# calchack.net
KiCad netlist of a schematic drawn in EAGLE
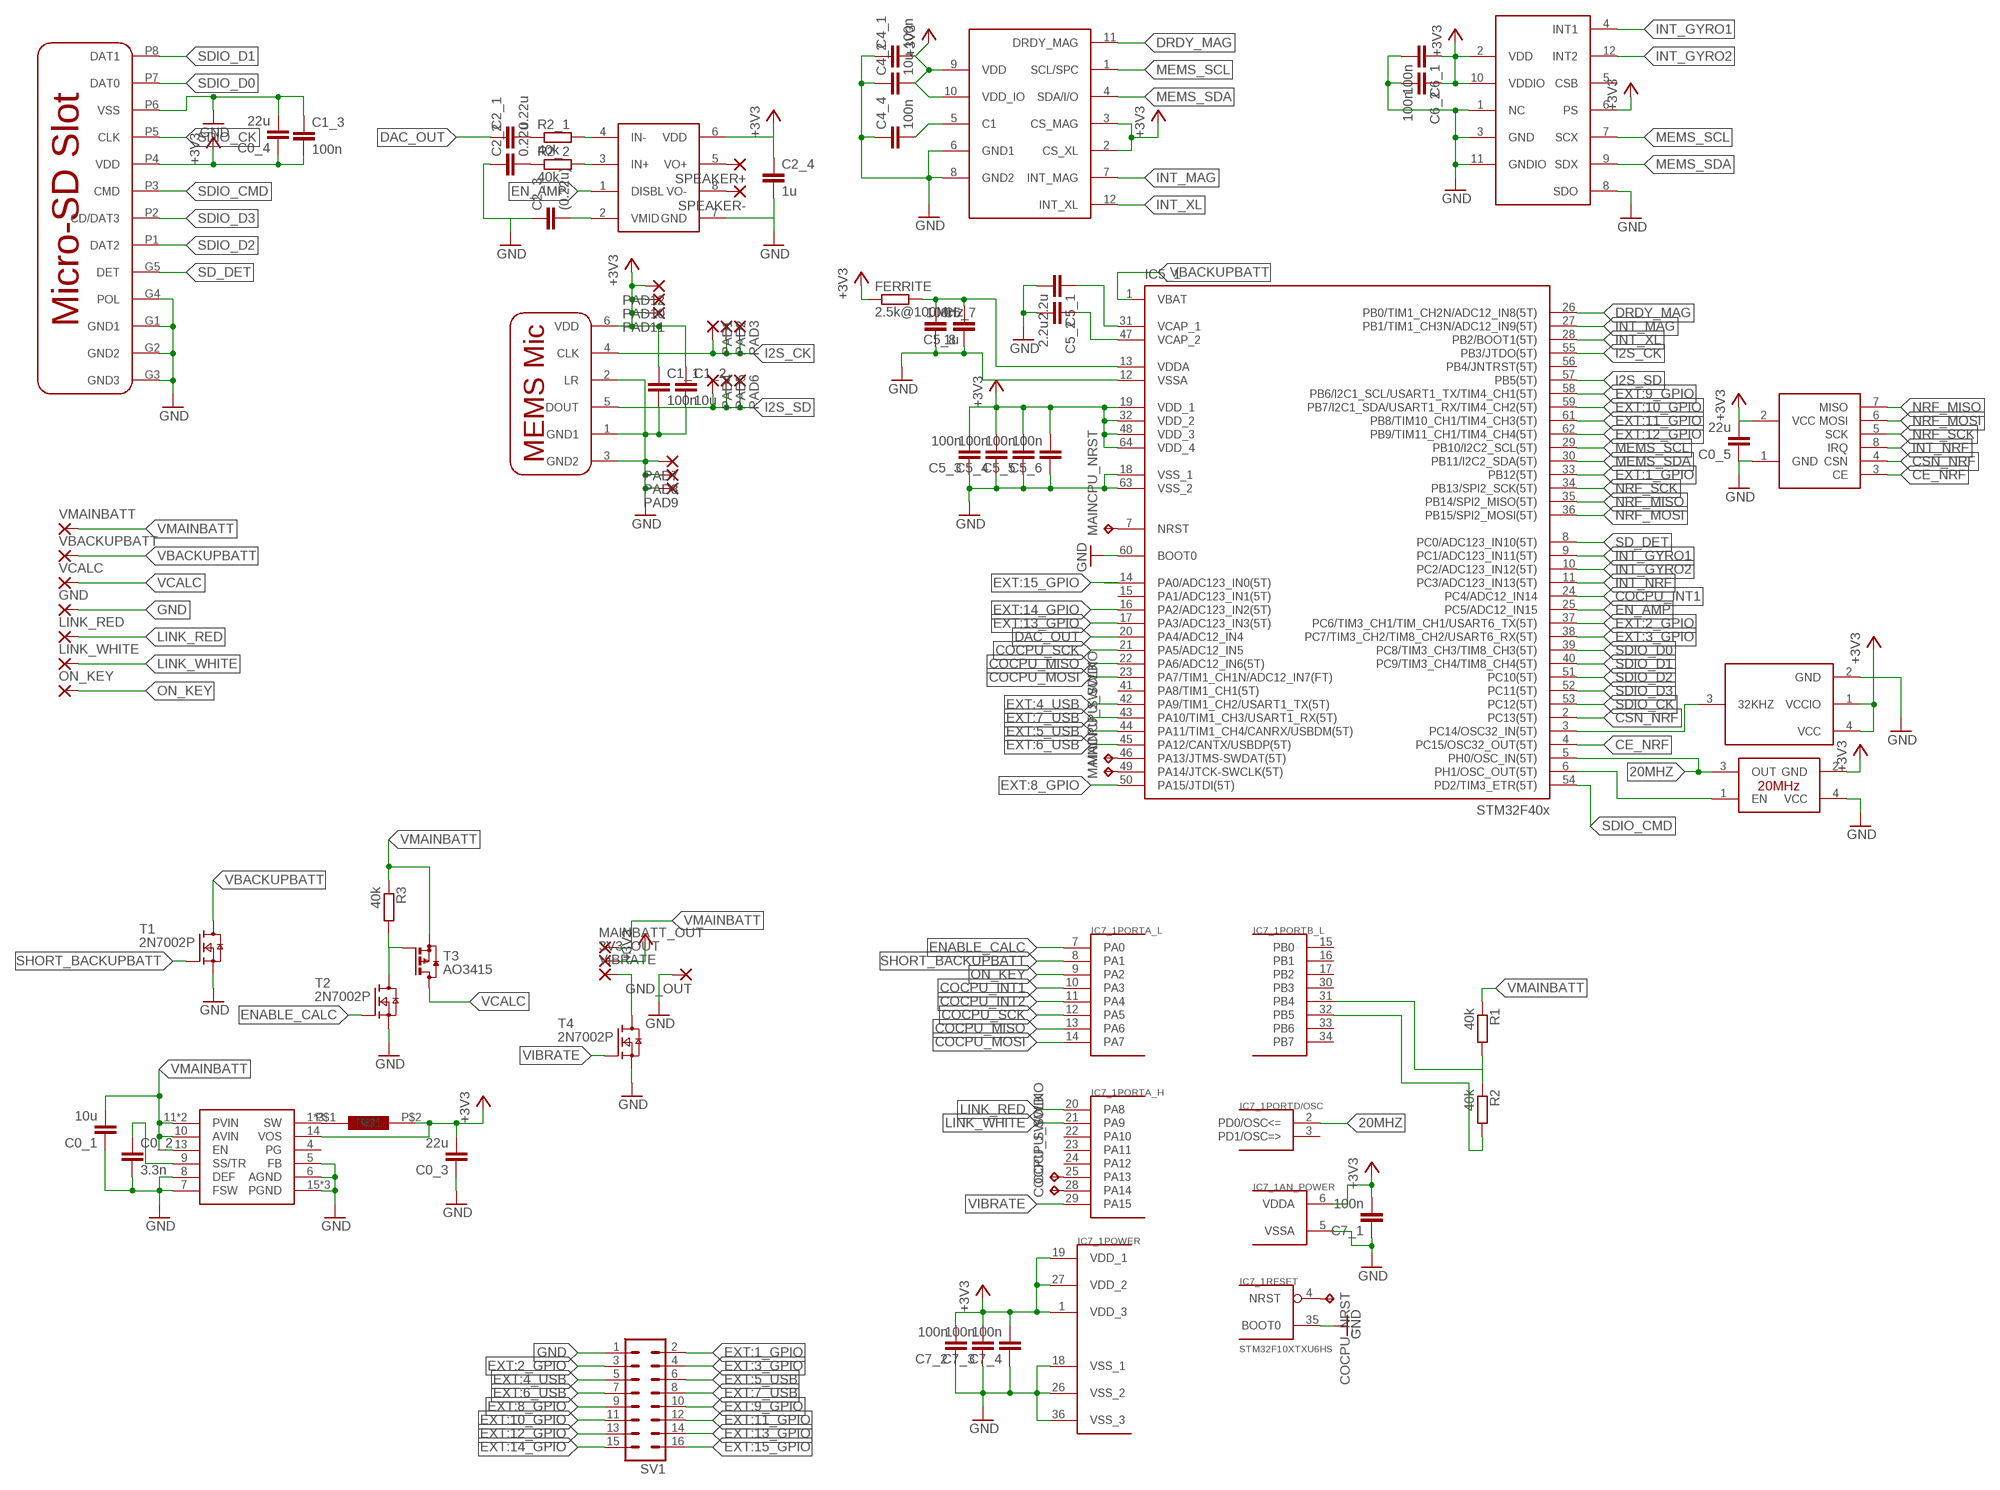
[diagram p0: schematic, sheet 1]

(export (version "E")
  (design (tool "Eeschema 10.0.6"))
  (components
    (comp (ref "3V3_OUT")
      (value "1,6/0,8")
      (footprint "eagle-import:1,6_0,8")
      (libsource (lib "eagle-import") (part "1,6/0,8"))
    )
    (comp (ref "C0_1")
      (value "10u")
      (footprint "eagle-import:C0805")
      (libsource (lib "eagle-import") (part "C-EUC0805"))
    )
    (comp (ref "C0_2")
      (value "3.3n")
      (footprint "eagle-import:C0603")
      (libsource (lib "eagle-import") (part "C-EUC0603"))
    )
    (comp (ref "C0_3")
      (value "22u")
      (footprint "eagle-import:C0805")
      (libsource (lib "eagle-import") (part "C-EUC0805"))
    )
    (comp (ref "C0_4")
      (value "22u")
      (footprint "eagle-import:C0805")
      (libsource (lib "eagle-import") (part "C-EUC0805"))
    )
    (comp (ref "C0_5")
      (value "22u")
      (footprint "eagle-import:C0805")
      (libsource (lib "eagle-import") (part "C-EUC0805"))
    )
    (comp (ref "C1_1")
      (value "100n")
      (footprint "eagle-import:C0603")
      (libsource (lib "eagle-import") (part "C-EUC0603"))
    )
    (comp (ref "C1_2")
      (value "10u")
      (footprint "eagle-import:C0603")
      (libsource (lib "eagle-import") (part "C-EUC0603"))
    )
    (comp (ref "C1_3")
      (value "100n")
      (footprint "eagle-import:C0603")
      (libsource (lib "eagle-import") (part "C-EUC0603"))
    )
    (comp (ref "C2_1")
      (value "0.22u")
      (footprint "eagle-import:C0603")
      (libsource (lib "eagle-import") (part "C-EUC0603"))
    )
    (comp (ref "C2_2")
      (value "0.22u")
      (footprint "eagle-import:C0603")
      (libsource (lib "eagle-import") (part "C-EUC0603"))
    )
    (comp (ref "C2_3")
      (value "(0.22u)")
      (footprint "eagle-import:C0603")
      (libsource (lib "eagle-import") (part "C-EUC0603"))
    )
    (comp (ref "C2_4")
      (value "1u")
      (footprint "eagle-import:C0603")
      (libsource (lib "eagle-import") (part "C-EUC0603"))
    )
    (comp (ref "C4_1")
      (value "100n")
      (footprint "eagle-import:C0603")
      (libsource (lib "eagle-import") (part "C-EUC0603"))
    )
    (comp (ref "C4_2")
      (value "10u")
      (footprint "eagle-import:C0603")
      (libsource (lib "eagle-import") (part "C-EUC0603"))
    )
    (comp (ref "C4_4")
      (value "100n")
      (footprint "eagle-import:C0603")
      (libsource (lib "eagle-import") (part "C-EUC0603"))
    )
    (comp (ref "C5_1")
      (value "2.2u")
      (footprint "eagle-import:C0603")
      (libsource (lib "eagle-import") (part "C-EUC0603"))
    )
    (comp (ref "C5_2")
      (value "2.2u")
      (footprint "eagle-import:C0603")
      (libsource (lib "eagle-import") (part "C-EUC0603"))
    )
    (comp (ref "C5_3")
      (value "100n")
      (footprint "eagle-import:C0603")
      (libsource (lib "eagle-import") (part "C-EUC0603"))
    )
    (comp (ref "C5_4")
      (value "100n")
      (footprint "eagle-import:C0603")
      (libsource (lib "eagle-import") (part "C-EUC0603"))
    )
    (comp (ref "C5_5")
      (value "100n")
      (footprint "eagle-import:C0603")
      (libsource (lib "eagle-import") (part "C-EUC0603"))
    )
    (comp (ref "C5_6")
      (value "100n")
      (footprint "eagle-import:C0603")
      (libsource (lib "eagle-import") (part "C-EUC0603"))
    )
    (comp (ref "C5_7")
      (value "1u")
      (footprint "eagle-import:C0603")
      (libsource (lib "eagle-import") (part "C-EUC0603"))
    )
    (comp (ref "C5_8")
      (value "100n")
      (footprint "eagle-import:C0603")
      (libsource (lib "eagle-import") (part "C-EUC0603"))
    )
    (comp (ref "C6_1")
      (value "100n")
      (footprint "eagle-import:C0603")
      (libsource (lib "eagle-import") (part "C-EUC0603"))
    )
    (comp (ref "C6_2")
      (value "100n")
      (footprint "eagle-import:C0603")
      (libsource (lib "eagle-import") (part "C-EUC0603"))
    )
    (comp (ref "C7_1")
      (value "100n")
      (footprint "eagle-import:C0603")
      (libsource (lib "eagle-import") (part "C-EUC0603"))
    )
    (comp (ref "C7_2")
      (value "100n")
      (footprint "eagle-import:C0603")
      (libsource (lib "eagle-import") (part "C-EUC0603"))
    )
    (comp (ref "C7_3")
      (value "100n")
      (footprint "eagle-import:C0603")
      (libsource (lib "eagle-import") (part "C-EUC0603"))
    )
    (comp (ref "C7_4")
      (value "100n")
      (footprint "eagle-import:C0603")
      (libsource (lib "eagle-import") (part "C-EUC0603"))
    )
    (comp (ref "COCPU_NRST")
      (value "TPTP10SQ")
      (footprint "eagle-import:TP10SQ")
      (libsource (lib "eagle-import") (part "TPTP10SQ"))
    )
    (comp (ref "COCPU_SWCLK")
      (value "TPTP10SQ")
      (footprint "eagle-import:TP10SQ")
      (libsource (lib "eagle-import") (part "TPTP10SQ"))
    )
    (comp (ref "COCPU_SWDIO")
      (value "TPTP10SQ")
      (footprint "eagle-import:TP10SQ")
      (libsource (lib "eagle-import") (part "TPTP10SQ"))
    )
    (comp (ref "FERRITE")
      (value "2.5k@100MHz")
      (footprint "eagle-import:R0603")
      (libsource (lib "eagle-import") (part "R-EU_R0603"))
    )
    (comp (ref "GND")
      (value "1,6/0,8")
      (footprint "eagle-import:1,6_0,8")
      (libsource (lib "eagle-import") (part "1,6/0,8"))
    )
    (comp (ref "GND_OUT")
      (value "1,6/0,8")
      (footprint "eagle-import:1,6_0,8")
      (libsource (lib "eagle-import") (part "1,6/0,8"))
    )
    (comp (ref "IC0_1")
      (value "TPS62142")
      (footprint "eagle-import:TPS62142")
      (libsource (lib "eagle-import") (part "TPS62142"))
    )
    (comp (ref "IC1_1")
      (value "MP45DT02")
      (footprint "eagle-import:MP45DT02")
      (libsource (lib "eagle-import") (part "MP45DT02"))
    )
    (comp (ref "IC2_1")
      (value "TPA6211A1")
      (footprint "eagle-import:TPA6211A1")
      (libsource (lib "eagle-import") (part "TPA6211A1"))
    )
    (comp (ref "IC3_1")
      (value "475710001")
      (footprint "eagle-import:475710001")
      (libsource (lib "eagle-import") (part "475710001"))
    )
    (comp (ref "IC4_1")
      (value "LSM303C")
      (footprint "eagle-import:LSM303C")
      (libsource (lib "eagle-import") (part "LSM303C"))
    )
    (comp (ref "IC5_1")
      (value "STM32F405R")
      (footprint "eagle-import:TQFP64")
      (libsource (lib "eagle-import") (part "STM32F405R"))
    )
    (comp (ref "IC6_1")
      (value "BMG160")
      (footprint "eagle-import:BMG160")
      (libsource (lib "eagle-import") (part "BMG160"))
    )
    (comp (ref "IC7_1")
      (value "STM32F10XTXU6HS")
      (footprint "eagle-import:VFQFPN36-HS")
      (libsource (lib "eagle-import") (part "STM32F10XTXU6HS"))
    )
    (comp (ref "L0_1")
      (value "IHLP1212BZER2R2M11")
      (footprint "eagle-import:IHLP1212BZER2R2M11")
      (libsource (lib "eagle-import") (part "IHLP1212BZER2R2M11"))
    )
    (comp (ref "LINK_RED")
      (value "1,6/0,8")
      (footprint "eagle-import:1,6_0,8")
      (libsource (lib "eagle-import") (part "1,6/0,8"))
    )
    (comp (ref "LINK_WHITE")
      (value "1,6/0,8")
      (footprint "eagle-import:1,6_0,8")
      (libsource (lib "eagle-import") (part "1,6/0,8"))
    )
    (comp (ref "MAINBATT_OUT")
      (value "1,6/0,8")
      (footprint "eagle-import:1,6_0,8")
      (libsource (lib "eagle-import") (part "1,6/0,8"))
    )
    (comp (ref "MAINCPU_NRST")
      (value "TPTP10SQ")
      (footprint "eagle-import:TP10SQ")
      (libsource (lib "eagle-import") (part "TPTP10SQ"))
    )
    (comp (ref "MAINCPU_SWCLK")
      (value "TPTP10SQ")
      (footprint "eagle-import:TP10SQ")
      (libsource (lib "eagle-import") (part "TPTP10SQ"))
    )
    (comp (ref "MAINCPU_SWDIO")
      (value "TPTP10SQ")
      (footprint "eagle-import:TP10SQ")
      (libsource (lib "eagle-import") (part "TPTP10SQ"))
    )
    (comp (ref "NRF24L01")
      (value "NRF24L01")
      (footprint "eagle-import:NRF24L01")
      (libsource (lib "eagle-import") (part "NRF24L01"))
    )
    (comp (ref "ON_KEY")
      (value "1,6/0,8")
      (footprint "eagle-import:1,6_0,8")
      (libsource (lib "eagle-import") (part "1,6/0,8"))
    )
    (comp (ref "OSC5_1")
      (value "SG-3030JC")
      (footprint "eagle-import:SG-3030JC")
      (libsource (lib "eagle-import") (part "SG-3030JC"))
    )
    (comp (ref "PAD1")
      (value "1,6/0,8")
      (footprint "eagle-import:1,6_0,8")
      (libsource (lib "eagle-import") (part "1,6/0,8"))
    )
    (comp (ref "PAD2")
      (value "1,6/0,8")
      (footprint "eagle-import:1,6_0,8")
      (libsource (lib "eagle-import") (part "1,6/0,8"))
    )
    (comp (ref "PAD3")
      (value "1,6/0,8")
      (footprint "eagle-import:1,6_0,8")
      (libsource (lib "eagle-import") (part "1,6/0,8"))
    )
    (comp (ref "PAD4")
      (value "1,6/0,8")
      (footprint "eagle-import:1,6_0,8")
      (libsource (lib "eagle-import") (part "1,6/0,8"))
    )
    (comp (ref "PAD5")
      (value "1,6/0,8")
      (footprint "eagle-import:1,6_0,8")
      (libsource (lib "eagle-import") (part "1,6/0,8"))
    )
    (comp (ref "PAD6")
      (value "1,6/0,8")
      (footprint "eagle-import:1,6_0,8")
      (libsource (lib "eagle-import") (part "1,6/0,8"))
    )
    (comp (ref "PAD7")
      (value "1,6/0,8")
      (footprint "eagle-import:1,6_0,8")
      (libsource (lib "eagle-import") (part "1,6/0,8"))
    )
    (comp (ref "PAD8")
      (value "1,6/0,8")
      (footprint "eagle-import:1,6_0,8")
      (libsource (lib "eagle-import") (part "1,6/0,8"))
    )
    (comp (ref "PAD9")
      (value "1,6/0,8")
      (footprint "eagle-import:1,6_0,8")
      (libsource (lib "eagle-import") (part "1,6/0,8"))
    )
    (comp (ref "PAD10")
      (value "1,6/0,8")
      (footprint "eagle-import:1,6_0,8")
      (libsource (lib "eagle-import") (part "1,6/0,8"))
    )
    (comp (ref "PAD11")
      (value "1,6/0,8")
      (footprint "eagle-import:1,6_0,8")
      (libsource (lib "eagle-import") (part "1,6/0,8"))
    )
    (comp (ref "PAD12")
      (value "1,6/0,8")
      (footprint "eagle-import:1,6_0,8")
      (libsource (lib "eagle-import") (part "1,6/0,8"))
    )
    (comp (ref "R1")
      (value "40k")
      (footprint "eagle-import:R0603")
      (libsource (lib "eagle-import") (part "R-EU_R0603"))
    )
    (comp (ref "R2")
      (value "40k")
      (footprint "eagle-import:R0603")
      (libsource (lib "eagle-import") (part "R-EU_R0603"))
    )
    (comp (ref "R2_1")
      (value "40k")
      (footprint "eagle-import:R0603")
      (libsource (lib "eagle-import") (part "R-EU_R0603"))
    )
    (comp (ref "R2_2")
      (value "40k")
      (footprint "eagle-import:R0603")
      (libsource (lib "eagle-import") (part "R-EU_R0603"))
    )
    (comp (ref "R3")
      (value "40k")
      (footprint "eagle-import:R0603")
      (libsource (lib "eagle-import") (part "R-EU_R0603"))
    )
    (comp (ref "SPEAKER+")
      (value "1,6/0,8")
      (footprint "eagle-import:1,6_0,8")
      (libsource (lib "eagle-import") (part "1,6/0,8"))
    )
    (comp (ref "SPEAKER-")
      (value "1,6/0,8")
      (footprint "eagle-import:1,6_0,8")
      (libsource (lib "eagle-import") (part "1,6/0,8"))
    )
    (comp (ref "SV1")
      (value "MA08-2")
      (footprint "eagle-import:MA08-2")
      (libsource (lib "eagle-import") (part "MA08-2"))
    )
    (comp (ref "T1")
      (value "2N7002P")
      (footprint "eagle-import:SOT23")
      (libsource (lib "eagle-import") (part "2N7002P"))
    )
    (comp (ref "T2")
      (value "2N7002P")
      (footprint "eagle-import:SOT23")
      (libsource (lib "eagle-import") (part "2N7002P"))
    )
    (comp (ref "T3")
      (value "AO3415")
      (footprint "eagle-import:AO3415")
      (libsource (lib "eagle-import") (part "AO3415"))
    )
    (comp (ref "T4")
      (value "2N7002P")
      (footprint "eagle-import:SOT23")
      (libsource (lib "eagle-import") (part "2N7002P"))
    )
    (comp (ref "U$1")
      (value "ASDMB-20.000MHZ-LC-T")
      (footprint "eagle-import:ASDMB-20.000MHZ-LC-T")
      (libsource (lib "eagle-import") (part "ASDMB-20.000MHZ-LC-T"))
    )
    (comp (ref "VBACKUPBATT")
      (value "1,6/0,8")
      (footprint "eagle-import:1,6_0,8")
      (libsource (lib "eagle-import") (part "1,6/0,8"))
    )
    (comp (ref "VCALC")
      (value "1,6/0,8")
      (footprint "eagle-import:1,6_0,8")
      (libsource (lib "eagle-import") (part "1,6/0,8"))
    )
    (comp (ref "VIBRATE")
      (value "1,6/0,8")
      (footprint "eagle-import:1,6_0,8")
      (libsource (lib "eagle-import") (part "1,6/0,8"))
    )
    (comp (ref "VMAINBATT")
      (value "1,6/0,8")
      (footprint "eagle-import:1,6_0,8")
      (libsource (lib "eagle-import") (part "1,6/0,8"))
    )
  )
  (nets
    (net (code "1") (name "+3V3") (class "Default")
      (node (ref "3V3_OUT") (pin "1") (pinfunction "P_1") (pintype "passive"))
      (node (ref "C0_3") (pin "2") (pinfunction "2_2") (pintype "passive"))
      (node (ref "C0_4") (pin "1") (pinfunction "1_1") (pintype "passive"))
      (node (ref "C0_5") (pin "2") (pinfunction "2_2") (pintype "passive"))
      (node (ref "C1_1") (pin "1") (pinfunction "1_1") (pintype "passive"))
      (node (ref "C1_2") (pin "1") (pinfunction "1_1") (pintype "passive"))
      (node (ref "C1_3") (pin "2") (pinfunction "2_2") (pintype "passive"))
      (node (ref "C2_4") (pin "1") (pinfunction "1_1") (pintype "passive"))
      (node (ref "C4_1") (pin "2") (pinfunction "2_2") (pintype "passive"))
      (node (ref "C4_2") (pin "2") (pinfunction "2_2") (pintype "passive"))
      (node (ref "C5_3") (pin "2") (pinfunction "2_2") (pintype "passive"))
      (node (ref "C5_4") (pin "2") (pinfunction "2_2") (pintype "passive"))
      (node (ref "C5_5") (pin "2") (pinfunction "2_2") (pintype "passive"))
      (node (ref "C5_6") (pin "2") (pinfunction "2_2") (pintype "passive"))
      (node (ref "C6_1") (pin "1") (pinfunction "1_1") (pintype "passive"))
      (node (ref "C6_2") (pin "1") (pinfunction "1_1") (pintype "passive"))
      (node (ref "C7_1") (pin "2") (pinfunction "2_2") (pintype "passive"))
      (node (ref "C7_2") (pin "2") (pinfunction "2_2") (pintype "passive"))
      (node (ref "C7_3") (pin "2") (pinfunction "2_2") (pintype "passive"))
      (node (ref "C7_4") (pin "2") (pinfunction "2_2") (pintype "passive"))
      (node (ref "FERRITE") (pin "1") (pinfunction "1_1") (pintype "passive"))
      (node (ref "IC0_1") (pin "14") (pinfunction "VOS_14") (pintype "bidirectional"))
      (node (ref "IC1_1") (pin "6") (pinfunction "VDD_6") (pintype "bidirectional"))
      (node (ref "IC2_1") (pin "6") (pinfunction "VDD_6") (pintype "bidirectional"))
      (node (ref "IC3_1") (pin "P4") (pinfunction "VDD_P4") (pintype "bidirectional"))
      (node (ref "IC4_1") (pin "10") (pinfunction "VDD_IO_10") (pintype "bidirectional"))
      (node (ref "IC4_1") (pin "2") (pinfunction "CS_XL_2") (pintype "bidirectional"))
      (node (ref "IC4_1") (pin "3") (pinfunction "CS_MAG_3") (pintype "bidirectional"))
      (node (ref "IC4_1") (pin "9") (pinfunction "VDD_9") (pintype "bidirectional"))
      (node (ref "IC5_1") (pin "19") (pinfunction "VDD_1_19") (pintype "bidirectional"))
      (node (ref "IC5_1") (pin "32") (pinfunction "VDD_2_32") (pintype "bidirectional"))
      (node (ref "IC5_1") (pin "48") (pinfunction "VDD_3_48") (pintype "bidirectional"))
      (node (ref "IC5_1") (pin "64") (pinfunction "VDD_4_64") (pintype "bidirectional"))
      (node (ref "IC6_1") (pin "10") (pinfunction "VDDIO_10") (pintype "bidirectional"))
      (node (ref "IC6_1") (pin "2") (pinfunction "VDD_2") (pintype "bidirectional"))
      (node (ref "IC6_1") (pin "6") (pinfunction "PS_6") (pintype "bidirectional"))
      (node (ref "IC7_1") (pin "1") (pinfunction "VDD_3_1") (pintype "power_in"))
      (node (ref "IC7_1") (pin "19") (pinfunction "VDD_1_19") (pintype "power_in"))
      (node (ref "IC7_1") (pin "27") (pinfunction "VDD_2_27") (pintype "power_in"))
      (node (ref "IC7_1") (pin "6") (pinfunction "VDDA_6") (pintype "power_in"))
      (node (ref "L0_1") (pin "P$2") (pinfunction "P$2_P$2") (pintype "bidirectional"))
      (node (ref "NRF24L01") (pin "2") (pinfunction "VCC_2") (pintype "bidirectional"))
      (node (ref "OSC5_1") (pin "1") (pinfunction "VCCIO_1") (pintype "bidirectional"))
      (node (ref "OSC5_1") (pin "4") (pinfunction "VCC_4") (pintype "bidirectional"))
      (node (ref "PAD10") (pin "1") (pinfunction "P_1") (pintype "passive"))
      (node (ref "PAD11") (pin "1") (pinfunction "P_1") (pintype "passive"))
      (node (ref "PAD12") (pin "1") (pinfunction "P_1") (pintype "passive"))
      (node (ref "U$1") (pin "2") (pinfunction "GND_2") (pintype "bidirectional"))
    )
    (net (code "2") (name "20MHZ") (class "Default")
      (node (ref "IC5_1") (pin "5") (pinfunction "PH0/OSC_IN(5T)_5") (pintype "bidirectional"))
      (node (ref "IC7_1") (pin "2") (pinfunction "PD0/OSC<=_2") (pintype "bidirectional"))
      (node (ref "U$1") (pin "3") (pinfunction "OUT_3") (pintype "bidirectional"))
    )
    (net (code "3") (name "CE_NRF") (class "Default")
      (node (ref "IC5_1") (pin "4") (pinfunction "PC15/OSC32_OUT(5T)_4") (pintype "bidirectional"))
      (node (ref "NRF24L01") (pin "3") (pinfunction "CE_3") (pintype "bidirectional"))
    )
    (net (code "4") (name "COCPU_INT1") (class "Default")
      (node (ref "IC5_1") (pin "24") (pinfunction "PC4/ADC12_IN14_24") (pintype "bidirectional"))
      (node (ref "IC7_1") (pin "10") (pinfunction "PA3_10") (pintype "bidirectional"))
    )
    (net (code "5") (name "COCPU_INT2") (class "Default")
      (node (ref "IC7_1") (pin "11") (pinfunction "PA4_11") (pintype "bidirectional"))
    )
    (net (code "6") (name "COCPU_MISO") (class "Default")
      (node (ref "IC5_1") (pin "22") (pinfunction "PA6/ADC12_IN6(5T)_22") (pintype "bidirectional"))
      (node (ref "IC7_1") (pin "13") (pinfunction "PA6_13") (pintype "bidirectional"))
    )
    (net (code "7") (name "COCPU_MOSI") (class "Default")
      (node (ref "IC5_1") (pin "23") (pinfunction "PA7/TIM1_CH1N/ADC12_IN7(FT)_23") (pintype "bidirectional"))
      (node (ref "IC7_1") (pin "14") (pinfunction "PA7_14") (pintype "bidirectional"))
    )
    (net (code "8") (name "COCPU_SCK") (class "Default")
      (node (ref "IC5_1") (pin "21") (pinfunction "PA5/ADC12_IN5_21") (pintype "bidirectional"))
      (node (ref "IC7_1") (pin "12") (pinfunction "PA5_12") (pintype "bidirectional"))
    )
    (net (code "9") (name "CSN_NRF") (class "Default")
      (node (ref "IC5_1") (pin "2") (pinfunction "PC13(5T)_2") (pintype "bidirectional"))
      (node (ref "NRF24L01") (pin "4") (pinfunction "CSN_4") (pintype "bidirectional"))
    )
    (net (code "10") (name "DAC_OUT") (class "Default")
      (node (ref "C2_1") (pin "1") (pinfunction "1_1") (pintype "passive"))
      (node (ref "IC5_1") (pin "20") (pinfunction "PA4/ADC12_IN4_20") (pintype "bidirectional"))
    )
    (net (code "11") (name "DRDY_MAG") (class "Default")
      (node (ref "IC4_1") (pin "11") (pinfunction "DRDY_MAG_11") (pintype "bidirectional"))
      (node (ref "IC5_1") (pin "26") (pinfunction "PB0/TIM1_CH2N/ADC12_IN8(5T)_26") (pintype "bidirectional"))
    )
    (net (code "12") (name "ENABLE_CALC") (class "Default")
      (node (ref "IC7_1") (pin "7") (pinfunction "PA0_7") (pintype "bidirectional"))
      (node (ref "T2") (pin "1") (pinfunction "G_1") (pintype "passive"))
    )
    (net (code "13") (name "EN_AMP") (class "Default")
      (node (ref "IC2_1") (pin "1") (pinfunction "DISBL_1") (pintype "bidirectional"))
      (node (ref "IC5_1") (pin "25") (pinfunction "PC5/ADC12_IN15_25") (pintype "bidirectional"))
    )
    (net (code "14") (name "EXT:1_GPIO") (class "Default")
      (node (ref "IC5_1") (pin "33") (pinfunction "PB12(5T)_33") (pintype "bidirectional"))
      (node (ref "SV1") (pin "2") (pinfunction "2_2") (pintype "passive"))
    )
    (net (code "15") (name "EXT:2_GPIO") (class "Default")
      (node (ref "IC5_1") (pin "37") (pinfunction "PC6/TIM3_CH1/TIM_CH1/USART6_TX(5T)_37") (pintype "bidirectional"))
      (node (ref "SV1") (pin "3") (pinfunction "3_3") (pintype "passive"))
    )
    (net (code "16") (name "EXT:3_GPIO") (class "Default")
      (node (ref "IC5_1") (pin "38") (pinfunction "PC7/TIM3_CH2/TIM8_CH2/USART6_RX(5T)_38") (pintype "bidirectional"))
      (node (ref "SV1") (pin "4") (pinfunction "4_4") (pintype "passive"))
    )
    (net (code "17") (name "EXT:4_USB") (class "Default")
      (node (ref "IC5_1") (pin "42") (pinfunction "PA9/TIM1_CH2/USART1_TX(5T)_42") (pintype "bidirectional"))
      (node (ref "SV1") (pin "5") (pinfunction "5_5") (pintype "passive"))
    )
    (net (code "18") (name "EXT:5_USB") (class "Default")
      (node (ref "IC5_1") (pin "44") (pinfunction "PA11/TIM1_CH4/CANRX/USBDM(5T)_44") (pintype "bidirectional"))
      (node (ref "SV1") (pin "6") (pinfunction "6_6") (pintype "passive"))
    )
    (net (code "19") (name "EXT:6_USB") (class "Default")
      (node (ref "IC5_1") (pin "45") (pinfunction "PA12/CANTX/USBDP(5T)_45") (pintype "bidirectional"))
      (node (ref "SV1") (pin "7") (pinfunction "7_7") (pintype "passive"))
    )
    (net (code "20") (name "EXT:7_USB") (class "Default")
      (node (ref "IC5_1") (pin "43") (pinfunction "PA10/TIM1_CH3/USART1_RX(5T)_43") (pintype "bidirectional"))
      (node (ref "SV1") (pin "8") (pinfunction "8_8") (pintype "passive"))
    )
    (net (code "21") (name "EXT:8_GPIO") (class "Default")
      (node (ref "IC5_1") (pin "50") (pinfunction "PA15/JTDI(5T)_50") (pintype "bidirectional"))
      (node (ref "SV1") (pin "9") (pinfunction "9_9") (pintype "passive"))
    )
    (net (code "22") (name "EXT:9_GPIO") (class "Default")
      (node (ref "IC5_1") (pin "58") (pinfunction "PB6/I2C1_SCL/USART1_TX/TIM4_CH1(5T)_58") (pintype "bidirectional"))
      (node (ref "SV1") (pin "10") (pinfunction "10_10") (pintype "passive"))
    )
    (net (code "23") (name "EXT:10_GPIO") (class "Default")
      (node (ref "IC5_1") (pin "59") (pinfunction "PB7/I2C1_SDA/USART1_RX/TIM4_CH2(5T)_59") (pintype "bidirectional"))
      (node (ref "SV1") (pin "11") (pinfunction "11_11") (pintype "passive"))
    )
    (net (code "24") (name "EXT:11_GPIO") (class "Default")
      (node (ref "IC5_1") (pin "61") (pinfunction "PB8/TIM10_CH1/TIM4_CH3(5T)_61") (pintype "bidirectional"))
      (node (ref "SV1") (pin "12") (pinfunction "12_12") (pintype "passive"))
    )
    (net (code "25") (name "EXT:12_GPIO") (class "Default")
      (node (ref "IC5_1") (pin "62") (pinfunction "PB9/TIM11_CH1/TIM4_CH4(5T)_62") (pintype "bidirectional"))
      (node (ref "SV1") (pin "13") (pinfunction "13_13") (pintype "passive"))
    )
    (net (code "26") (name "EXT:13_GPIO") (class "Default")
      (node (ref "IC5_1") (pin "17") (pinfunction "PA3/ADC123_IN3(5T)_17") (pintype "bidirectional"))
      (node (ref "SV1") (pin "14") (pinfunction "14_14") (pintype "passive"))
    )
    (net (code "27") (name "EXT:14_GPIO") (class "Default")
      (node (ref "IC5_1") (pin "16") (pinfunction "PA2/ADC123_IN2(5T)_16") (pintype "bidirectional"))
      (node (ref "SV1") (pin "15") (pinfunction "15_15") (pintype "passive"))
    )
    (net (code "28") (name "EXT:15_GPIO") (class "Default")
      (node (ref "IC5_1") (pin "14") (pinfunction "PA0/ADC123_IN0(5T)_14") (pintype "bidirectional"))
      (node (ref "SV1") (pin "16") (pinfunction "16_16") (pintype "passive"))
    )
    (net (code "29") (name "GND") (class "Default")
      (node (ref "C0_1") (pin "1") (pinfunction "1_1") (pintype "passive"))
      (node (ref "C0_2") (pin "2") (pinfunction "2_2") (pintype "passive"))
      (node (ref "C0_3") (pin "1") (pinfunction "1_1") (pintype "passive"))
      (node (ref "C0_4") (pin "2") (pinfunction "2_2") (pintype "passive"))
      (node (ref "C0_5") (pin "1") (pinfunction "1_1") (pintype "passive"))
      (node (ref "C1_1") (pin "2") (pinfunction "2_2") (pintype "passive"))
      (node (ref "C1_2") (pin "2") (pinfunction "2_2") (pintype "passive"))
      (node (ref "C1_3") (pin "1") (pinfunction "1_1") (pintype "passive"))
      (node (ref "C2_2") (pin "1") (pinfunction "1_1") (pintype "passive"))
      (node (ref "C2_3") (pin "1") (pinfunction "1_1") (pintype "passive"))
      (node (ref "C2_4") (pin "2") (pinfunction "2_2") (pintype "passive"))
      (node (ref "C4_1") (pin "1") (pinfunction "1_1") (pintype "passive"))
      (node (ref "C4_2") (pin "1") (pinfunction "1_1") (pintype "passive"))
      (node (ref "C4_4") (pin "1") (pinfunction "1_1") (pintype "passive"))
      (node (ref "C5_1") (pin "2") (pinfunction "2_2") (pintype "passive"))
      (node (ref "C5_2") (pin "2") (pinfunction "2_2") (pintype "passive"))
      (node (ref "C5_3") (pin "1") (pinfunction "1_1") (pintype "passive"))
      (node (ref "C5_4") (pin "1") (pinfunction "1_1") (pintype "passive"))
      (node (ref "C5_5") (pin "1") (pinfunction "1_1") (pintype "passive"))
      (node (ref "C5_6") (pin "1") (pinfunction "1_1") (pintype "passive"))
      (node (ref "C5_7") (pin "2") (pinfunction "2_2") (pintype "passive"))
      (node (ref "C5_8") (pin "1") (pinfunction "1_1") (pintype "passive"))
      (node (ref "C6_1") (pin "2") (pinfunction "2_2") (pintype "passive"))
      (node (ref "C6_2") (pin "2") (pinfunction "2_2") (pintype "passive"))
      (node (ref "C7_1") (pin "1") (pinfunction "1_1") (pintype "passive"))
      (node (ref "C7_2") (pin "1") (pinfunction "1_1") (pintype "passive"))
      (node (ref "C7_3") (pin "1") (pinfunction "1_1") (pintype "passive"))
      (node (ref "C7_4") (pin "1") (pinfunction "1_1") (pintype "passive"))
      (node (ref "GND") (pin "1") (pinfunction "P_1") (pintype "passive"))
      (node (ref "GND_OUT") (pin "1") (pinfunction "P_1") (pintype "passive"))
      (node (ref "IC0_1") (pin "15") (pinfunction "PGND_15") (pintype "bidirectional"))
      (node (ref "IC0_1") (pin "16") (pinfunction "PGND_16") (pintype "bidirectional"))
      (node (ref "IC0_1") (pin "5") (pinfunction "FB_5") (pintype "bidirectional"))
      (node (ref "IC0_1") (pin "6") (pinfunction "AGND_6") (pintype "bidirectional"))
      (node (ref "IC0_1") (pin "7") (pinfunction "FSW_7") (pintype "bidirectional"))
      (node (ref "IC0_1") (pin "8") (pinfunction "DEF_8") (pintype "bidirectional"))
      (node (ref "IC0_1") (pin "TH") (pinfunction "PGND_TH") (pintype "bidirectional"))
      (node (ref "IC1_1") (pin "1") (pinfunction "GND1_1") (pintype "bidirectional"))
      (node (ref "IC1_1") (pin "2") (pinfunction "LR_2") (pintype "bidirectional"))
      (node (ref "IC1_1") (pin "3") (pinfunction "GND2_3") (pintype "bidirectional"))
      (node (ref "IC2_1") (pin "7") (pinfunction "GND_7") (pintype "bidirectional"))
      (node (ref "IC3_1") (pin "G1") (pinfunction "GND1_G1") (pintype "bidirectional"))
      (node (ref "IC3_1") (pin "G2") (pinfunction "GND2_G2") (pintype "bidirectional"))
      (node (ref "IC3_1") (pin "G3") (pinfunction "GND3_G3") (pintype "bidirectional"))
      (node (ref "IC3_1") (pin "G4") (pinfunction "POL_G4") (pintype "bidirectional"))
      (node (ref "IC3_1") (pin "P6") (pinfunction "VSS_P6") (pintype "bidirectional"))
      (node (ref "IC4_1") (pin "6") (pinfunction "GND1_6") (pintype "bidirectional"))
      (node (ref "IC4_1") (pin "8") (pinfunction "GND2_8") (pintype "bidirectional"))
      (node (ref "IC5_1") (pin "12") (pinfunction "VSSA_12") (pintype "bidirectional"))
      (node (ref "IC5_1") (pin "18") (pinfunction "VSS_1_18") (pintype "bidirectional"))
      (node (ref "IC5_1") (pin "60") (pinfunction "BOOT0_60") (pintype "bidirectional"))
      (node (ref "IC5_1") (pin "63") (pinfunction "VSS_2_63") (pintype "bidirectional"))
      (node (ref "IC6_1") (pin "1") (pinfunction "NC_1") (pintype "bidirectional"))
      (node (ref "IC6_1") (pin "11") (pinfunction "GNDIO_11") (pintype "bidirectional"))
      (node (ref "IC6_1") (pin "3") (pinfunction "GND_3") (pintype "bidirectional"))
      (node (ref "IC6_1") (pin "8") (pinfunction "SDO_8") (pintype "bidirectional"))
      (node (ref "IC7_1") (pin "18") (pinfunction "VSS_1_18") (pintype "power_in"))
      (node (ref "IC7_1") (pin "26") (pinfunction "VSS_2_26") (pintype "power_in"))
      (node (ref "IC7_1") (pin "35") (pinfunction "BOOT0_35") (pintype "input"))
      (node (ref "IC7_1") (pin "36") (pinfunction "VSS_3_36") (pintype "power_in"))
      (node (ref "IC7_1") (pin "5") (pinfunction "VSSA_5") (pintype "power_in"))
      (node (ref "NRF24L01") (pin "1") (pinfunction "GND_1") (pintype "bidirectional"))
      (node (ref "OSC5_1") (pin "2") (pinfunction "GND_2") (pintype "bidirectional"))
      (node (ref "PAD7") (pin "1") (pinfunction "P_1") (pintype "passive"))
      (node (ref "PAD8") (pin "1") (pinfunction "P_1") (pintype "passive"))
      (node (ref "PAD9") (pin "1") (pinfunction "P_1") (pintype "passive"))
      (node (ref "SV1") (pin "1") (pinfunction "1_1") (pintype "passive"))
      (node (ref "T1") (pin "2") (pinfunction "S_2") (pintype "passive"))
      (node (ref "T2") (pin "2") (pinfunction "S_2") (pintype "passive"))
      (node (ref "T4") (pin "2") (pinfunction "S_2") (pintype "passive"))
      (node (ref "U$1") (pin "4") (pinfunction "VCC_4") (pintype "bidirectional"))
    )
    (net (code "30") (name "I2S_CK") (class "Default")
      (node (ref "IC1_1") (pin "4") (pinfunction "CLK_4") (pintype "bidirectional"))
      (node (ref "IC5_1") (pin "55") (pinfunction "PB3/JTDO(5T)_55") (pintype "bidirectional"))
      (node (ref "PAD1") (pin "1") (pinfunction "P_1") (pintype "passive"))
      (node (ref "PAD2") (pin "1") (pinfunction "P_1") (pintype "passive"))
      (node (ref "PAD3") (pin "1") (pinfunction "P_1") (pintype "passive"))
    )
    (net (code "31") (name "I2S_SD") (class "Default")
      (node (ref "IC1_1") (pin "5") (pinfunction "DOUT_5") (pintype "bidirectional"))
      (node (ref "IC5_1") (pin "57") (pinfunction "PB5(5T)_57") (pintype "bidirectional"))
      (node (ref "PAD4") (pin "1") (pinfunction "P_1") (pintype "passive"))
      (node (ref "PAD5") (pin "1") (pinfunction "P_1") (pintype "passive"))
      (node (ref "PAD6") (pin "1") (pinfunction "P_1") (pintype "passive"))
    )
    (net (code "32") (name "INT_GYRO1") (class "Default")
      (node (ref "IC5_1") (pin "9") (pinfunction "PC1/ADC123_IN11(5T)_9") (pintype "bidirectional"))
      (node (ref "IC6_1") (pin "4") (pinfunction "INT1_4") (pintype "bidirectional"))
    )
    (net (code "33") (name "INT_GYRO2") (class "Default")
      (node (ref "IC5_1") (pin "10") (pinfunction "PC2/ADC123_IN12(5T)_10") (pintype "bidirectional"))
      (node (ref "IC6_1") (pin "12") (pinfunction "INT2_12") (pintype "bidirectional"))
    )
    (net (code "34") (name "INT_MAG") (class "Default")
      (node (ref "IC4_1") (pin "7") (pinfunction "INT_MAG_7") (pintype "bidirectional"))
      (node (ref "IC5_1") (pin "27") (pinfunction "PB1/TIM1_CH3N/ADC12_IN9(5T)_27") (pintype "bidirectional"))
    )
    (net (code "35") (name "INT_NRF") (class "Default")
      (node (ref "IC5_1") (pin "11") (pinfunction "PC3/ADC123_IN13(5T)_11") (pintype "bidirectional"))
      (node (ref "NRF24L01") (pin "8") (pinfunction "IRQ_8") (pintype "bidirectional"))
    )
    (net (code "36") (name "INT_XL") (class "Default")
      (node (ref "IC4_1") (pin "12") (pinfunction "INT_XL_12") (pintype "bidirectional"))
      (node (ref "IC5_1") (pin "28") (pinfunction "PB2/BOOT1(5T)_28") (pintype "bidirectional"))
    )
    (net (code "37") (name "LINK_RED") (class "Default")
      (node (ref "IC7_1") (pin "20") (pinfunction "PA8_20") (pintype "bidirectional"))
      (node (ref "LINK_RED") (pin "1") (pinfunction "P_1") (pintype "passive"))
    )
    (net (code "38") (name "LINK_WHITE") (class "Default")
      (node (ref "IC7_1") (pin "21") (pinfunction "PA9_21") (pintype "bidirectional"))
      (node (ref "LINK_WHITE") (pin "1") (pinfunction "P_1") (pintype "passive"))
    )
    (net (code "39") (name "MEMS_SCL") (class "Default")
      (node (ref "IC4_1") (pin "1") (pinfunction "SCL/SPC_1") (pintype "bidirectional"))
      (node (ref "IC5_1") (pin "29") (pinfunction "PB10/I2C2_SCL(5T)_29") (pintype "bidirectional"))
      (node (ref "IC6_1") (pin "7") (pinfunction "SCX_7") (pintype "bidirectional"))
    )
    (net (code "40") (name "MEMS_SDA") (class "Default")
      (node (ref "IC4_1") (pin "4") (pinfunction "SDA/I/O_4") (pintype "bidirectional"))
      (node (ref "IC5_1") (pin "30") (pinfunction "PB11/I2C2_SDA(5T)_30") (pintype "bidirectional"))
      (node (ref "IC6_1") (pin "9") (pinfunction "SDX_9") (pintype "bidirectional"))
    )
    (net (code "41") (name "NRF_MISO") (class "Default")
      (node (ref "IC5_1") (pin "35") (pinfunction "PB14/SPI2_MISO(5T)_35") (pintype "bidirectional"))
      (node (ref "NRF24L01") (pin "7") (pinfunction "MISO_7") (pintype "bidirectional"))
    )
    (net (code "42") (name "NRF_MOSI") (class "Default")
      (node (ref "IC5_1") (pin "36") (pinfunction "PB15/SPI2_MOSI(5T)_36") (pintype "bidirectional"))
      (node (ref "NRF24L01") (pin "6") (pinfunction "MOSI_6") (pintype "bidirectional"))
    )
    (net (code "43") (name "NRF_SCK") (class "Default")
      (node (ref "IC5_1") (pin "34") (pinfunction "PB13/SPI2_SCK(5T)_34") (pintype "bidirectional"))
      (node (ref "NRF24L01") (pin "5") (pinfunction "SCK_5") (pintype "bidirectional"))
    )
    (net (code "44") (name "Net-(C2_1-Pad2)") (class "Default")
      (node (ref "C2_1") (pin "2") (pinfunction "2_2") (pintype "passive"))
      (node (ref "R2_1") (pin "1") (pinfunction "1_1") (pintype "passive"))
    )
    (net (code "45") (name "Net-(C2_2-Pad2)") (class "Default")
      (node (ref "C2_2") (pin "2") (pinfunction "2_2") (pintype "passive"))
      (node (ref "R2_2") (pin "1") (pinfunction "1_1") (pintype "passive"))
    )
    (net (code "46") (name "Net-(IC0_1-SS{slash}TR)") (class "Default")
      (node (ref "C0_2") (pin "1") (pinfunction "1_1") (pintype "passive"))
      (node (ref "IC0_1") (pin "9") (pinfunction "SS/TR_9") (pintype "bidirectional"))
    )
    (net (code "47") (name "Net-(IC0_1-SW-Pad1)") (class "Default")
      (node (ref "IC0_1") (pin "1") (pinfunction "SW_1") (pintype "bidirectional"))
      (node (ref "IC0_1") (pin "2") (pinfunction "SW_2") (pintype "bidirectional"))
      (node (ref "IC0_1") (pin "3") (pinfunction "SW_3") (pintype "bidirectional"))
      (node (ref "L0_1") (pin "P$1") (pinfunction "P$1_P$1") (pintype "bidirectional"))
    )
    (net (code "48") (name "Net-(IC2_1-IN+)") (class "Default")
      (node (ref "IC2_1") (pin "3") (pinfunction "IN+_3") (pintype "bidirectional"))
      (node (ref "R2_2") (pin "2") (pinfunction "2_2") (pintype "passive"))
    )
    (net (code "49") (name "Net-(IC2_1-IN-)") (class "Default")
      (node (ref "IC2_1") (pin "4") (pinfunction "IN-_4") (pintype "bidirectional"))
      (node (ref "R2_1") (pin "2") (pinfunction "2_2") (pintype "passive"))
    )
    (net (code "50") (name "Net-(IC2_1-VMID)") (class "Default")
      (node (ref "C2_3") (pin "2") (pinfunction "2_2") (pintype "passive"))
      (node (ref "IC2_1") (pin "2") (pinfunction "VMID_2") (pintype "bidirectional"))
    )
    (net (code "51") (name "Net-(IC2_1-VO+)") (class "Default")
      (node (ref "IC2_1") (pin "5") (pinfunction "VO+_5") (pintype "bidirectional"))
      (node (ref "SPEAKER+") (pin "1") (pinfunction "P_1") (pintype "passive"))
    )
    (net (code "52") (name "Net-(IC2_1-VO-)") (class "Default")
      (node (ref "IC2_1") (pin "8") (pinfunction "VO-_8") (pintype "bidirectional"))
      (node (ref "SPEAKER-") (pin "1") (pinfunction "P_1") (pintype "passive"))
    )
    (net (code "53") (name "Net-(IC4_1-C1)") (class "Default")
      (node (ref "C4_4") (pin "2") (pinfunction "2_2") (pintype "passive"))
      (node (ref "IC4_1") (pin "5") (pinfunction "C1_5") (pintype "bidirectional"))
    )
    (net (code "54") (name "Net-(IC5_1-NRST)") (class "Default")
      (node (ref "IC5_1") (pin "7") (pinfunction "NRST_7") (pintype "bidirectional"))
      (node (ref "MAINCPU_NRST") (pin "TP") (pinfunction "TP_TP") (pintype "input"))
    )
    (net (code "55") (name "Net-(IC5_1-PA13{slash}JTMS-SWDAT(5T))") (class "Default")
      (node (ref "IC5_1") (pin "46") (pinfunction "PA13/JTMS-SWDAT(5T)_46") (pintype "bidirectional"))
      (node (ref "MAINCPU_SWDIO") (pin "TP") (pinfunction "TP_TP") (pintype "input"))
    )
    (net (code "56") (name "Net-(IC5_1-PA14{slash}JTCK-SWCLK(5T))") (class "Default")
      (node (ref "IC5_1") (pin "49") (pinfunction "PA14/JTCK-SWCLK(5T)_49") (pintype "bidirectional"))
      (node (ref "MAINCPU_SWCLK") (pin "TP") (pinfunction "TP_TP") (pintype "input"))
    )
    (net (code "57") (name "Net-(IC5_1-PC14{slash}OSC32_IN(5T))") (class "Default")
      (node (ref "IC5_1") (pin "3") (pinfunction "PC14/OSC32_IN(5T)_3") (pintype "bidirectional"))
      (node (ref "OSC5_1") (pin "3") (pinfunction "32KHZ_3") (pintype "bidirectional"))
    )
    (net (code "58") (name "Net-(IC5_1-PH1{slash}OSC_OUT(5T))") (class "Default")
      (node (ref "IC5_1") (pin "6") (pinfunction "PH1/OSC_OUT(5T)_6") (pintype "bidirectional"))
      (node (ref "U$1") (pin "1") (pinfunction "EN_1") (pintype "bidirectional"))
    )
    (net (code "59") (name "Net-(IC5_1-VCAP_1)") (class "Default")
      (node (ref "C5_1") (pin "1") (pinfunction "1_1") (pintype "passive"))
      (node (ref "IC5_1") (pin "31") (pinfunction "VCAP_1_31") (pintype "bidirectional"))
    )
    (net (code "60") (name "Net-(IC5_1-VCAP_2)") (class "Default")
      (node (ref "C5_2") (pin "1") (pinfunction "1_1") (pintype "passive"))
      (node (ref "IC5_1") (pin "47") (pinfunction "VCAP_2_47") (pintype "bidirectional"))
    )
    (net (code "61") (name "Net-(IC5_1-VDDA)") (class "Default")
      (node (ref "C5_7") (pin "1") (pinfunction "1_1") (pintype "passive"))
      (node (ref "C5_8") (pin "2") (pinfunction "2_2") (pintype "passive"))
      (node (ref "FERRITE") (pin "2") (pinfunction "2_2") (pintype "passive"))
      (node (ref "IC5_1") (pin "13") (pinfunction "VDDA_13") (pintype "bidirectional"))
    )
    (net (code "62") (name "Net-(IC7_1B-PA13)") (class "Default")
      (node (ref "COCPU_SWDIO") (pin "TP") (pinfunction "TP_TP") (pintype "input"))
      (node (ref "IC7_1") (pin "25") (pinfunction "PA13_25") (pintype "bidirectional"))
    )
    (net (code "63") (name "Net-(IC7_1B-PA14)") (class "Default")
      (node (ref "COCPU_SWCLK") (pin "TP") (pinfunction "TP_TP") (pintype "input"))
      (node (ref "IC7_1") (pin "28") (pinfunction "PA14_28") (pintype "bidirectional"))
    )
    (net (code "64") (name "Net-(IC7_1D-PB4)") (class "Default")
      (node (ref "IC7_1") (pin "31") (pinfunction "PB4_31") (pintype "bidirectional"))
      (node (ref "R1") (pin "2") (pinfunction "2_2") (pintype "passive"))
      (node (ref "R2") (pin "1") (pinfunction "1_1") (pintype "passive"))
    )
    (net (code "65") (name "Net-(IC7_1D-PB5)") (class "Default")
      (node (ref "IC7_1") (pin "32") (pinfunction "PB5_32") (pintype "bidirectional"))
      (node (ref "R2") (pin "2") (pinfunction "2_2") (pintype "passive"))
    )
    (net (code "66") (name "Net-(IC7_1G-NRST)") (class "Default")
      (node (ref "COCPU_NRST") (pin "TP") (pinfunction "TP_TP") (pintype "input"))
      (node (ref "IC7_1") (pin "4") (pinfunction "NRST_4") (pintype "input"))
    )
    (net (code "67") (name "Net-(T2-D)") (class "Default")
      (node (ref "R3") (pin "2") (pinfunction "2_2") (pintype "passive"))
      (node (ref "T2") (pin "3") (pinfunction "D_3") (pintype "passive"))
      (node (ref "T3") (pin "1") (pinfunction "G_1") (pintype "passive"))
    )
    (net (code "68") (name "Net-(T4-D)") (class "Default")
      (node (ref "T4") (pin "3") (pinfunction "D_3") (pintype "passive"))
      (node (ref "VIBRATE") (pin "1") (pinfunction "P_1") (pintype "passive"))
    )
    (net (code "69") (name "ON_KEY") (class "Default")
      (node (ref "IC7_1") (pin "9") (pinfunction "PA2_9") (pintype "bidirectional"))
      (node (ref "ON_KEY") (pin "1") (pinfunction "P_1") (pintype "passive"))
    )
    (net (code "70") (name "SDIO_CK") (class "Default")
      (node (ref "IC3_1") (pin "P5") (pinfunction "CLK_P5") (pintype "bidirectional"))
      (node (ref "IC5_1") (pin "53") (pinfunction "PC12(5T)_53") (pintype "bidirectional"))
    )
    (net (code "71") (name "SDIO_CMD") (class "Default")
      (node (ref "IC3_1") (pin "P3") (pinfunction "CMD_P3") (pintype "bidirectional"))
      (node (ref "IC5_1") (pin "54") (pinfunction "PD2/TIM3_ETR(5T)_54") (pintype "bidirectional"))
    )
    (net (code "72") (name "SDIO_D0") (class "Default")
      (node (ref "IC3_1") (pin "P7") (pinfunction "DAT0_P7") (pintype "bidirectional"))
      (node (ref "IC5_1") (pin "39") (pinfunction "PC8/TIM3_CH3/TIM8_CH3(5T)_39") (pintype "bidirectional"))
    )
    (net (code "73") (name "SDIO_D1") (class "Default")
      (node (ref "IC3_1") (pin "P8") (pinfunction "DAT1_P8") (pintype "bidirectional"))
      (node (ref "IC5_1") (pin "40") (pinfunction "PC9/TIM3_CH4/TIM8_CH4(5T)_40") (pintype "bidirectional"))
    )
    (net (code "74") (name "SDIO_D2") (class "Default")
      (node (ref "IC3_1") (pin "P1") (pinfunction "DAT2_P1") (pintype "bidirectional"))
      (node (ref "IC5_1") (pin "51") (pinfunction "PC10(5T)_51") (pintype "bidirectional"))
    )
    (net (code "75") (name "SDIO_D3") (class "Default")
      (node (ref "IC3_1") (pin "P2") (pinfunction "CD/DAT3_P2") (pintype "bidirectional"))
      (node (ref "IC5_1") (pin "52") (pinfunction "PC11(5T)_52") (pintype "bidirectional"))
    )
    (net (code "76") (name "SD_DET") (class "Default")
      (node (ref "IC3_1") (pin "G5") (pinfunction "DET_G5") (pintype "bidirectional"))
      (node (ref "IC5_1") (pin "8") (pinfunction "PC0/ADC123_IN10(5T)_8") (pintype "bidirectional"))
    )
    (net (code "77") (name "SHORT_BACKUPBATT") (class "Default")
      (node (ref "IC7_1") (pin "8") (pinfunction "PA1_8") (pintype "bidirectional"))
      (node (ref "T1") (pin "1") (pinfunction "G_1") (pintype "passive"))
    )
    (net (code "78") (name "VBACKUPBATT") (class "Default")
      (node (ref "IC5_1") (pin "1") (pinfunction "VBAT_1") (pintype "bidirectional"))
      (node (ref "T1") (pin "3") (pinfunction "D_3") (pintype "passive"))
      (node (ref "VBACKUPBATT") (pin "1") (pinfunction "P_1") (pintype "passive"))
    )
    (net (code "79") (name "VCALC") (class "Default")
      (node (ref "T3") (pin "3") (pinfunction "D_3") (pintype "passive"))
      (node (ref "VCALC") (pin "1") (pinfunction "P_1") (pintype "passive"))
    )
    (net (code "80") (name "VIBRATE") (class "Default")
      (node (ref "IC7_1") (pin "29") (pinfunction "PA15_29") (pintype "bidirectional"))
      (node (ref "T4") (pin "1") (pinfunction "G_1") (pintype "passive"))
    )
    (net (code "81") (name "VMAINBATT") (class "Default")
      (node (ref "C0_1") (pin "2") (pinfunction "2_2") (pintype "passive"))
      (node (ref "IC0_1") (pin "10") (pinfunction "AVIN_10") (pintype "bidirectional"))
      (node (ref "IC0_1") (pin "11") (pinfunction "PVIN_11") (pintype "bidirectional"))
      (node (ref "IC0_1") (pin "12") (pinfunction "PVIN_12") (pintype "bidirectional"))
      (node (ref "IC0_1") (pin "13") (pinfunction "EN_13") (pintype "bidirectional"))
      (node (ref "MAINBATT_OUT") (pin "1") (pinfunction "P_1") (pintype "passive"))
      (node (ref "R1") (pin "1") (pinfunction "1_1") (pintype "passive"))
      (node (ref "R3") (pin "1") (pinfunction "1_1") (pintype "passive"))
      (node (ref "T3") (pin "2") (pinfunction "S_2") (pintype "passive"))
      (node (ref "VMAINBATT") (pin "1") (pinfunction "P_1") (pintype "passive"))
    )
    (net (code "82") (name "unconnected-(IC0_1-PG-Pad4)") (class "Default")
      (node (ref "IC0_1") (pin "4") (pinfunction "PG_4") (pintype "bidirectional"))
    )
    (net (code "83") (name "unconnected-(IC5_1-PA1{slash}ADC123_IN1(5T)-Pad15)") (class "Default")
      (node (ref "IC5_1") (pin "15") (pinfunction "PA1/ADC123_IN1(5T)_15") (pintype "bidirectional"))
    )
    (net (code "84") (name "unconnected-(IC5_1-PA8{slash}TIM1_CH1(5T)-Pad41)") (class "Default")
      (node (ref "IC5_1") (pin "41") (pinfunction "PA8/TIM1_CH1(5T)_41") (pintype "bidirectional"))
    )
    (net (code "85") (name "unconnected-(IC5_1-PB4{slash}JNTRST(5T)-Pad56)") (class "Default")
      (node (ref "IC5_1") (pin "56") (pinfunction "PB4/JNTRST(5T)_56") (pintype "bidirectional"))
    )
    (net (code "86") (name "unconnected-(IC6_1-CSB-Pad5)") (class "Default")
      (node (ref "IC6_1") (pin "5") (pinfunction "CSB_5") (pintype "bidirectional"))
    )
    (net (code "87") (name "unconnected-(IC7_1B-PA10-Pad22)") (class "Default")
      (node (ref "IC7_1") (pin "22") (pinfunction "PA10_22") (pintype "bidirectional"))
    )
    (net (code "88") (name "unconnected-(IC7_1B-PA11-Pad23)") (class "Default")
      (node (ref "IC7_1") (pin "23") (pinfunction "PA11_23") (pintype "bidirectional"))
    )
    (net (code "89") (name "unconnected-(IC7_1B-PA12-Pad24)") (class "Default")
      (node (ref "IC7_1") (pin "24") (pinfunction "PA12_24") (pintype "bidirectional"))
    )
    (net (code "90") (name "unconnected-(IC7_1D-PB0-Pad15)") (class "Default")
      (node (ref "IC7_1") (pin "15") (pinfunction "PB0_15") (pintype "bidirectional"))
    )
    (net (code "91") (name "unconnected-(IC7_1D-PB1-Pad16)") (class "Default")
      (node (ref "IC7_1") (pin "16") (pinfunction "PB1_16") (pintype "bidirectional"))
    )
    (net (code "92") (name "unconnected-(IC7_1D-PB2-Pad17)") (class "Default")
      (node (ref "IC7_1") (pin "17") (pinfunction "PB2_17") (pintype "bidirectional"))
    )
    (net (code "93") (name "unconnected-(IC7_1D-PB3-Pad30)") (class "Default")
      (node (ref "IC7_1") (pin "30") (pinfunction "PB3_30") (pintype "bidirectional"))
    )
    (net (code "94") (name "unconnected-(IC7_1D-PB6-Pad33)") (class "Default")
      (node (ref "IC7_1") (pin "33") (pinfunction "PB6_33") (pintype "bidirectional"))
    )
    (net (code "95") (name "unconnected-(IC7_1D-PB7-Pad34)") (class "Default")
      (node (ref "IC7_1") (pin "34") (pinfunction "PB7_34") (pintype "bidirectional"))
    )
    (net (code "96") (name "unconnected-(IC7_1E-PD1{slash}OSC=>-Pad3)") (class "Default")
      (node (ref "IC7_1") (pin "3") (pinfunction "PD1/OSC=>_3") (pintype "bidirectional"))
    )
  )
)
